# inverterboard-v1.net
KiCad netlist of a schematic drawn in EAGLE
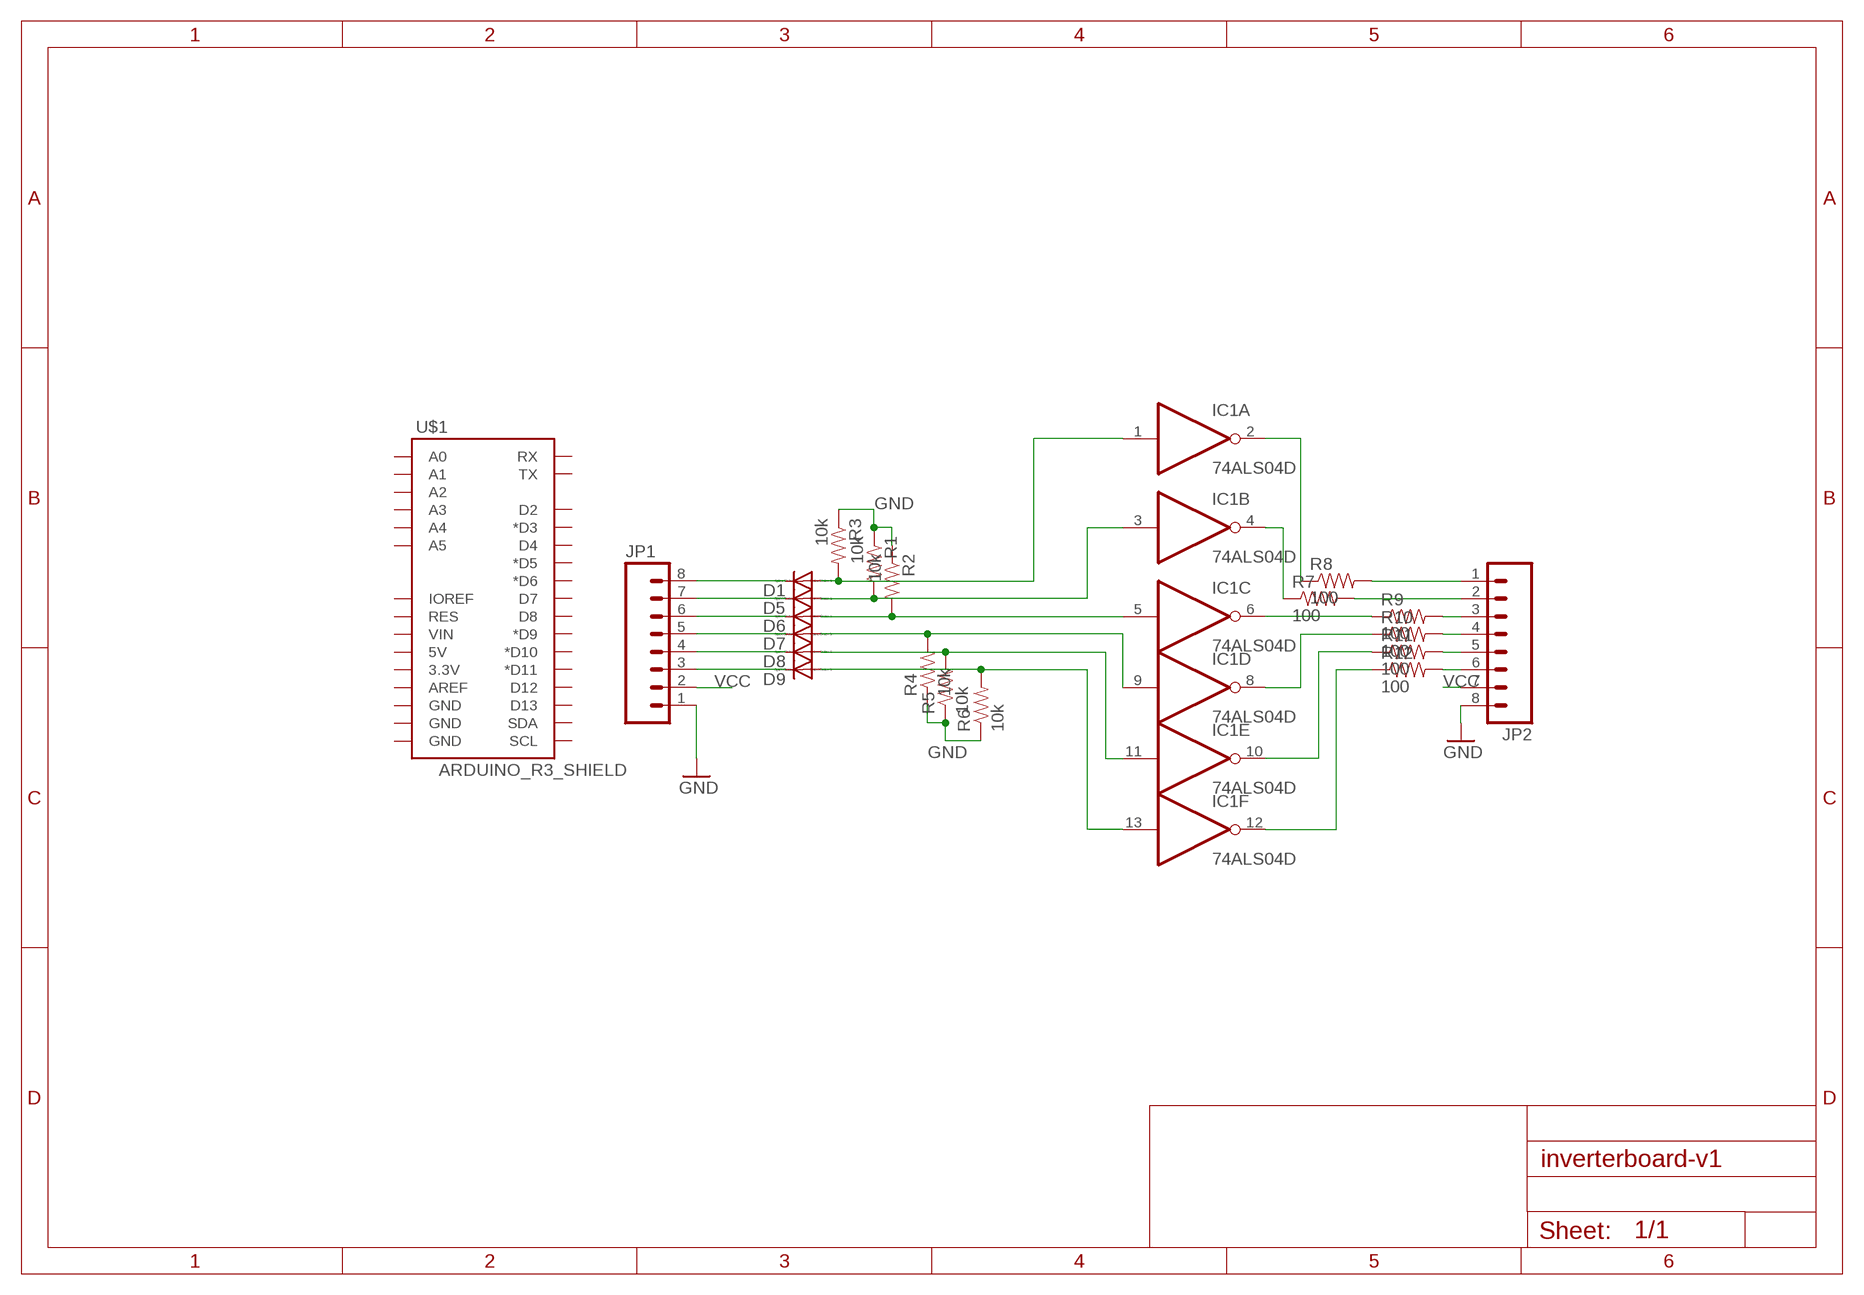
[diagram p0: schematic, sheet 1]

(export (version "E")
  (design (tool "Eeschema 10.0.6"))
  (components
    (comp (ref "D1")
      (value "DIODE-DO-214AC")
      (footprint "eagle-import:DO-214AC")
      (libsource (lib "eagle-import") (part "DIODE-DO-214AC"))
    )
    (comp (ref "D5")
      (value "DIODE-DO-214AC")
      (footprint "eagle-import:DO-214AC")
      (libsource (lib "eagle-import") (part "DIODE-DO-214AC"))
    )
    (comp (ref "D6")
      (value "DIODE-DO-214AC")
      (footprint "eagle-import:DO-214AC")
      (libsource (lib "eagle-import") (part "DIODE-DO-214AC"))
    )
    (comp (ref "D7")
      (value "DIODE-DO-214AC")
      (footprint "eagle-import:DO-214AC")
      (libsource (lib "eagle-import") (part "DIODE-DO-214AC"))
    )
    (comp (ref "D8")
      (value "DIODE-DO-214AC")
      (footprint "eagle-import:DO-214AC")
      (libsource (lib "eagle-import") (part "DIODE-DO-214AC"))
    )
    (comp (ref "D9")
      (value "DIODE-DO-214AC")
      (footprint "eagle-import:DO-214AC")
      (libsource (lib "eagle-import") (part "DIODE-DO-214AC"))
    )
    (comp (ref "IC1")
      (value "74ALS04D")
      (footprint "eagle-import:SO14")
      (libsource (lib "eagle-import") (part "7404DALS"))
    )
    (comp (ref "JP1")
      (value "M081X08")
      (footprint "eagle-import:1X08")
      (libsource (lib "eagle-import") (part "M081X08"))
    )
    (comp (ref "JP2")
      (value "M081X08")
      (footprint "eagle-import:1X08")
      (libsource (lib "eagle-import") (part "M081X08"))
    )
    (comp (ref "R1")
      (value "10k")
      (footprint "eagle-import:0603-RES")
      (libsource (lib "eagle-import") (part "RESISTOR0603"))
    )
    (comp (ref "R2")
      (value "10k")
      (footprint "eagle-import:0603-RES")
      (libsource (lib "eagle-import") (part "RESISTOR0603"))
    )
    (comp (ref "R3")
      (value "10k")
      (footprint "eagle-import:0603-RES")
      (libsource (lib "eagle-import") (part "RESISTOR0603"))
    )
    (comp (ref "R4")
      (value "10k")
      (footprint "eagle-import:0603-RES")
      (libsource (lib "eagle-import") (part "RESISTOR0603"))
    )
    (comp (ref "R5")
      (value "10k")
      (footprint "eagle-import:0603-RES")
      (libsource (lib "eagle-import") (part "RESISTOR0603"))
    )
    (comp (ref "R6")
      (value "10k")
      (footprint "eagle-import:0603-RES")
      (libsource (lib "eagle-import") (part "RESISTOR0603"))
    )
    (comp (ref "R7")
      (value "100")
      (footprint "eagle-import:0603-RES")
      (libsource (lib "eagle-import") (part "RESISTOR0603"))
    )
    (comp (ref "R8")
      (value "100")
      (footprint "eagle-import:0603-RES")
      (libsource (lib "eagle-import") (part "RESISTOR0603"))
    )
    (comp (ref "R9")
      (value "100")
      (footprint "eagle-import:0603-RES")
      (libsource (lib "eagle-import") (part "RESISTOR0603"))
    )
    (comp (ref "R10")
      (value "100")
      (footprint "eagle-import:0603-RES")
      (libsource (lib "eagle-import") (part "RESISTOR0603"))
    )
    (comp (ref "R11")
      (value "100")
      (footprint "eagle-import:0603-RES")
      (libsource (lib "eagle-import") (part "RESISTOR0603"))
    )
    (comp (ref "R12")
      (value "100")
      (footprint "eagle-import:0603-RES")
      (libsource (lib "eagle-import") (part "RESISTOR0603"))
    )
    (comp (ref "U$1")
      (value "ARDUINO_R3_SHIELD")
      (footprint "eagle-import:UNO_R3_SHIELD")
      (libsource (lib "eagle-import") (part "ARDUINO_R3_SHIELD"))
    )
  )
  (nets
    (net (code "1") (name "/VCC") (class "Default")
      (node (ref "JP1") (pin "2") (pinfunction "2_2") (pintype "passive"))
      (node (ref "JP2") (pin "7") (pinfunction "7_7") (pintype "passive"))
    )
    (net (code "2") (name "GND") (class "Default")
      (node (ref "JP1") (pin "1") (pinfunction "1_1") (pintype "passive"))
      (node (ref "JP2") (pin "8") (pinfunction "8_8") (pintype "passive"))
      (node (ref "R1") (pin "1") (pinfunction "1_1") (pintype "passive"))
      (node (ref "R2") (pin "1") (pinfunction "1_1") (pintype "passive"))
      (node (ref "R3") (pin "1") (pinfunction "1_1") (pintype "passive"))
      (node (ref "R4") (pin "1") (pinfunction "1_1") (pintype "passive"))
      (node (ref "R5") (pin "1") (pinfunction "1_1") (pintype "passive"))
      (node (ref "R6") (pin "1") (pinfunction "1_1") (pintype "passive"))
    )
    (net (code "3") (name "Net-(D1-PadC)") (class "Default")
      (node (ref "D1") (pin "C") (pinfunction "C_C") (pintype "passive"))
      (node (ref "JP1") (pin "8") (pinfunction "8_8") (pintype "passive"))
    )
    (net (code "4") (name "Net-(D5-PadC)") (class "Default")
      (node (ref "D5") (pin "C") (pinfunction "C_C") (pintype "passive"))
      (node (ref "JP1") (pin "7") (pinfunction "7_7") (pintype "passive"))
    )
    (net (code "5") (name "Net-(D6-PadC)") (class "Default")
      (node (ref "D6") (pin "C") (pinfunction "C_C") (pintype "passive"))
      (node (ref "JP1") (pin "6") (pinfunction "6_6") (pintype "passive"))
    )
    (net (code "6") (name "Net-(D7-PadC)") (class "Default")
      (node (ref "D7") (pin "C") (pinfunction "C_C") (pintype "passive"))
      (node (ref "JP1") (pin "5") (pinfunction "5_5") (pintype "passive"))
    )
    (net (code "7") (name "Net-(D8-PadC)") (class "Default")
      (node (ref "D8") (pin "C") (pinfunction "C_C") (pintype "passive"))
      (node (ref "JP1") (pin "4") (pinfunction "4_4") (pintype "passive"))
    )
    (net (code "8") (name "Net-(D9-PadC)") (class "Default")
      (node (ref "D9") (pin "C") (pinfunction "C_C") (pintype "passive"))
      (node (ref "JP1") (pin "3") (pinfunction "3_3") (pintype "passive"))
    )
    (net (code "9") (name "Net-(IC1A-I)") (class "Default")
      (node (ref "D1") (pin "A") (pinfunction "A_A") (pintype "passive"))
      (node (ref "IC1") (pin "1") (pinfunction "I_1") (pintype "input"))
      (node (ref "R3") (pin "2") (pinfunction "2_2") (pintype "passive"))
    )
    (net (code "10") (name "Net-(IC1A-O)") (class "Default")
      (node (ref "IC1") (pin "2") (pinfunction "O_2") (pintype "output"))
      (node (ref "R8") (pin "1") (pinfunction "1_1") (pintype "passive"))
    )
    (net (code "11") (name "Net-(IC1B-I)") (class "Default")
      (node (ref "D5") (pin "A") (pinfunction "A_A") (pintype "passive"))
      (node (ref "IC1") (pin "3") (pinfunction "I_3") (pintype "input"))
      (node (ref "R1") (pin "2") (pinfunction "2_2") (pintype "passive"))
    )
    (net (code "12") (name "Net-(IC1B-O)") (class "Default")
      (node (ref "IC1") (pin "4") (pinfunction "O_4") (pintype "output"))
      (node (ref "R7") (pin "1") (pinfunction "1_1") (pintype "passive"))
    )
    (net (code "13") (name "Net-(IC1C-I)") (class "Default")
      (node (ref "D6") (pin "A") (pinfunction "A_A") (pintype "passive"))
      (node (ref "IC1") (pin "5") (pinfunction "I_5") (pintype "input"))
      (node (ref "R2") (pin "2") (pinfunction "2_2") (pintype "passive"))
    )
    (net (code "14") (name "Net-(IC1C-O)") (class "Default")
      (node (ref "IC1") (pin "6") (pinfunction "O_6") (pintype "output"))
      (node (ref "R9") (pin "1") (pinfunction "1_1") (pintype "passive"))
    )
    (net (code "15") (name "Net-(IC1D-I)") (class "Default")
      (node (ref "D7") (pin "A") (pinfunction "A_A") (pintype "passive"))
      (node (ref "IC1") (pin "9") (pinfunction "I_9") (pintype "input"))
      (node (ref "R4") (pin "2") (pinfunction "2_2") (pintype "passive"))
    )
    (net (code "16") (name "Net-(IC1D-O)") (class "Default")
      (node (ref "IC1") (pin "8") (pinfunction "O_8") (pintype "output"))
      (node (ref "R10") (pin "1") (pinfunction "1_1") (pintype "passive"))
    )
    (net (code "17") (name "Net-(IC1E-I)") (class "Default")
      (node (ref "D8") (pin "A") (pinfunction "A_A") (pintype "passive"))
      (node (ref "IC1") (pin "11") (pinfunction "I_11") (pintype "input"))
      (node (ref "R5") (pin "2") (pinfunction "2_2") (pintype "passive"))
    )
    (net (code "18") (name "Net-(IC1E-O)") (class "Default")
      (node (ref "IC1") (pin "10") (pinfunction "O_10") (pintype "output"))
      (node (ref "R11") (pin "1") (pinfunction "1_1") (pintype "passive"))
    )
    (net (code "19") (name "Net-(IC1F-I)") (class "Default")
      (node (ref "D9") (pin "A") (pinfunction "A_A") (pintype "passive"))
      (node (ref "IC1") (pin "13") (pinfunction "I_13") (pintype "input"))
      (node (ref "R6") (pin "2") (pinfunction "2_2") (pintype "passive"))
    )
    (net (code "20") (name "Net-(IC1F-O)") (class "Default")
      (node (ref "IC1") (pin "12") (pinfunction "O_12") (pintype "output"))
      (node (ref "R12") (pin "1") (pinfunction "1_1") (pintype "passive"))
    )
    (net (code "21") (name "Net-(JP2-Pad1)") (class "Default")
      (node (ref "JP2") (pin "1") (pinfunction "1_1") (pintype "passive"))
      (node (ref "R8") (pin "2") (pinfunction "2_2") (pintype "passive"))
    )
    (net (code "22") (name "Net-(JP2-Pad2)") (class "Default")
      (node (ref "JP2") (pin "2") (pinfunction "2_2") (pintype "passive"))
      (node (ref "R7") (pin "2") (pinfunction "2_2") (pintype "passive"))
    )
    (net (code "23") (name "Net-(JP2-Pad3)") (class "Default")
      (node (ref "JP2") (pin "3") (pinfunction "3_3") (pintype "passive"))
      (node (ref "R9") (pin "2") (pinfunction "2_2") (pintype "passive"))
    )
    (net (code "24") (name "Net-(JP2-Pad4)") (class "Default")
      (node (ref "JP2") (pin "4") (pinfunction "4_4") (pintype "passive"))
      (node (ref "R10") (pin "2") (pinfunction "2_2") (pintype "passive"))
    )
    (net (code "25") (name "Net-(JP2-Pad5)") (class "Default")
      (node (ref "JP2") (pin "5") (pinfunction "5_5") (pintype "passive"))
      (node (ref "R11") (pin "2") (pinfunction "2_2") (pintype "passive"))
    )
    (net (code "26") (name "Net-(JP2-Pad6)") (class "Default")
      (node (ref "JP2") (pin "6") (pinfunction "6_6") (pintype "passive"))
      (node (ref "R12") (pin "2") (pinfunction "2_2") (pintype "passive"))
    )
    (net (code "27") (name "unconnected-(U$1-*D3-PadD3)") (class "Default")
      (node (ref "U$1") (pin "D3") (pinfunction "*D3_D3") (pintype "bidirectional"))
    )
    (net (code "28") (name "unconnected-(U$1-*D5-PadD5)") (class "Default")
      (node (ref "U$1") (pin "D5") (pinfunction "*D5_D5") (pintype "bidirectional"))
    )
    (net (code "29") (name "unconnected-(U$1-*D6-PadD6)") (class "Default")
      (node (ref "U$1") (pin "D6") (pinfunction "*D6_D6") (pintype "bidirectional"))
    )
    (net (code "30") (name "unconnected-(U$1-*D9-PadD9)") (class "Default")
      (node (ref "U$1") (pin "D9") (pinfunction "*D9_D9") (pintype "bidirectional"))
    )
    (net (code "31") (name "unconnected-(U$1-*D10-PadD10)") (class "Default")
      (node (ref "U$1") (pin "D10") (pinfunction "*D10_D10") (pintype "bidirectional"))
    )
    (net (code "32") (name "unconnected-(U$1-*D11-PadD11)") (class "Default")
      (node (ref "U$1") (pin "D11") (pinfunction "*D11_D11") (pintype "bidirectional"))
    )
    (net (code "33") (name "unconnected-(U$1-GND-PadGND@0)") (class "Default")
      (node (ref "U$1") (pin "GND@0") (pinfunction "GND_GND@0") (pintype "bidirectional"))
    )
    (net (code "34") (name "unconnected-(U$1-GND-PadGND@1)") (class "Default")
      (node (ref "U$1") (pin "GND@1") (pinfunction "GND_GND@1") (pintype "bidirectional"))
    )
    (net (code "35") (name "unconnected-(U$1-GND-PadGND@2)") (class "Default")
      (node (ref "U$1") (pin "GND@2") (pinfunction "GND_GND@2") (pintype "bidirectional"))
    )
    (net (code "36") (name "unconnected-(U$1-Pad3.3V)") (class "Default")
      (node (ref "U$1") (pin "3.3V") (pinfunction "3.3V_3.3V") (pintype "bidirectional"))
    )
    (net (code "37") (name "unconnected-(U$1-Pad5V)") (class "Default")
      (node (ref "U$1") (pin "5V") (pinfunction "5V_5V") (pintype "bidirectional"))
    )
    (net (code "38") (name "unconnected-(U$1-PadA0)") (class "Default")
      (node (ref "U$1") (pin "A0") (pinfunction "A0_A0") (pintype "bidirectional"))
    )
    (net (code "39") (name "unconnected-(U$1-PadA1)") (class "Default")
      (node (ref "U$1") (pin "A1") (pinfunction "A1_A1") (pintype "bidirectional"))
    )
    (net (code "40") (name "unconnected-(U$1-PadA2)") (class "Default")
      (node (ref "U$1") (pin "A2") (pinfunction "A2_A2") (pintype "bidirectional"))
    )
    (net (code "41") (name "unconnected-(U$1-PadA3)") (class "Default")
      (node (ref "U$1") (pin "A3") (pinfunction "A3_A3") (pintype "bidirectional"))
    )
    (net (code "42") (name "unconnected-(U$1-PadA4)") (class "Default")
      (node (ref "U$1") (pin "A4") (pinfunction "A4_A4") (pintype "bidirectional"))
    )
    (net (code "43") (name "unconnected-(U$1-PadA5)") (class "Default")
      (node (ref "U$1") (pin "A5") (pinfunction "A5_A5") (pintype "bidirectional"))
    )
    (net (code "44") (name "unconnected-(U$1-PadAREF)") (class "Default")
      (node (ref "U$1") (pin "AREF") (pinfunction "AREF_AREF") (pintype "bidirectional"))
    )
    (net (code "45") (name "unconnected-(U$1-PadD2)") (class "Default")
      (node (ref "U$1") (pin "D2") (pinfunction "D2_D2") (pintype "bidirectional"))
    )
    (net (code "46") (name "unconnected-(U$1-PadD4)") (class "Default")
      (node (ref "U$1") (pin "D4") (pinfunction "D4_D4") (pintype "bidirectional"))
    )
    (net (code "47") (name "unconnected-(U$1-PadD7)") (class "Default")
      (node (ref "U$1") (pin "D7") (pinfunction "D7_D7") (pintype "bidirectional"))
    )
    (net (code "48") (name "unconnected-(U$1-PadD8)") (class "Default")
      (node (ref "U$1") (pin "D8") (pinfunction "D8_D8") (pintype "bidirectional"))
    )
    (net (code "49") (name "unconnected-(U$1-PadD12)") (class "Default")
      (node (ref "U$1") (pin "D12") (pinfunction "D12_D12") (pintype "bidirectional"))
    )
    (net (code "50") (name "unconnected-(U$1-PadD13)") (class "Default")
      (node (ref "U$1") (pin "D13") (pinfunction "D13_D13") (pintype "bidirectional"))
    )
    (net (code "51") (name "unconnected-(U$1-PadIOREF)") (class "Default")
      (node (ref "U$1") (pin "IOREF") (pinfunction "IOREF_IOREF") (pintype "bidirectional"))
    )
    (net (code "52") (name "unconnected-(U$1-PadRES)") (class "Default")
      (node (ref "U$1") (pin "RES") (pinfunction "RES_RES") (pintype "bidirectional"))
    )
    (net (code "53") (name "unconnected-(U$1-PadRX)") (class "Default")
      (node (ref "U$1") (pin "RX") (pinfunction "RX_RX") (pintype "bidirectional"))
    )
    (net (code "54") (name "unconnected-(U$1-PadSCL)") (class "Default")
      (node (ref "U$1") (pin "SCL") (pinfunction "SCL_SCL") (pintype "bidirectional"))
    )
    (net (code "55") (name "unconnected-(U$1-PadSDA)") (class "Default")
      (node (ref "U$1") (pin "SDA") (pinfunction "SDA_SDA") (pintype "bidirectional"))
    )
    (net (code "56") (name "unconnected-(U$1-PadTX)") (class "Default")
      (node (ref "U$1") (pin "TX") (pinfunction "TX_TX") (pintype "bidirectional"))
    )
    (net (code "57") (name "unconnected-(U$1-PadVIN)") (class "Default")
      (node (ref "U$1") (pin "VIN") (pinfunction "VIN_VIN") (pintype "bidirectional"))
    )
  )
)
